# Adafruit_ESP32-S3_8MB_No_PSRAM.net
KiCad netlist of a schematic drawn in EAGLE
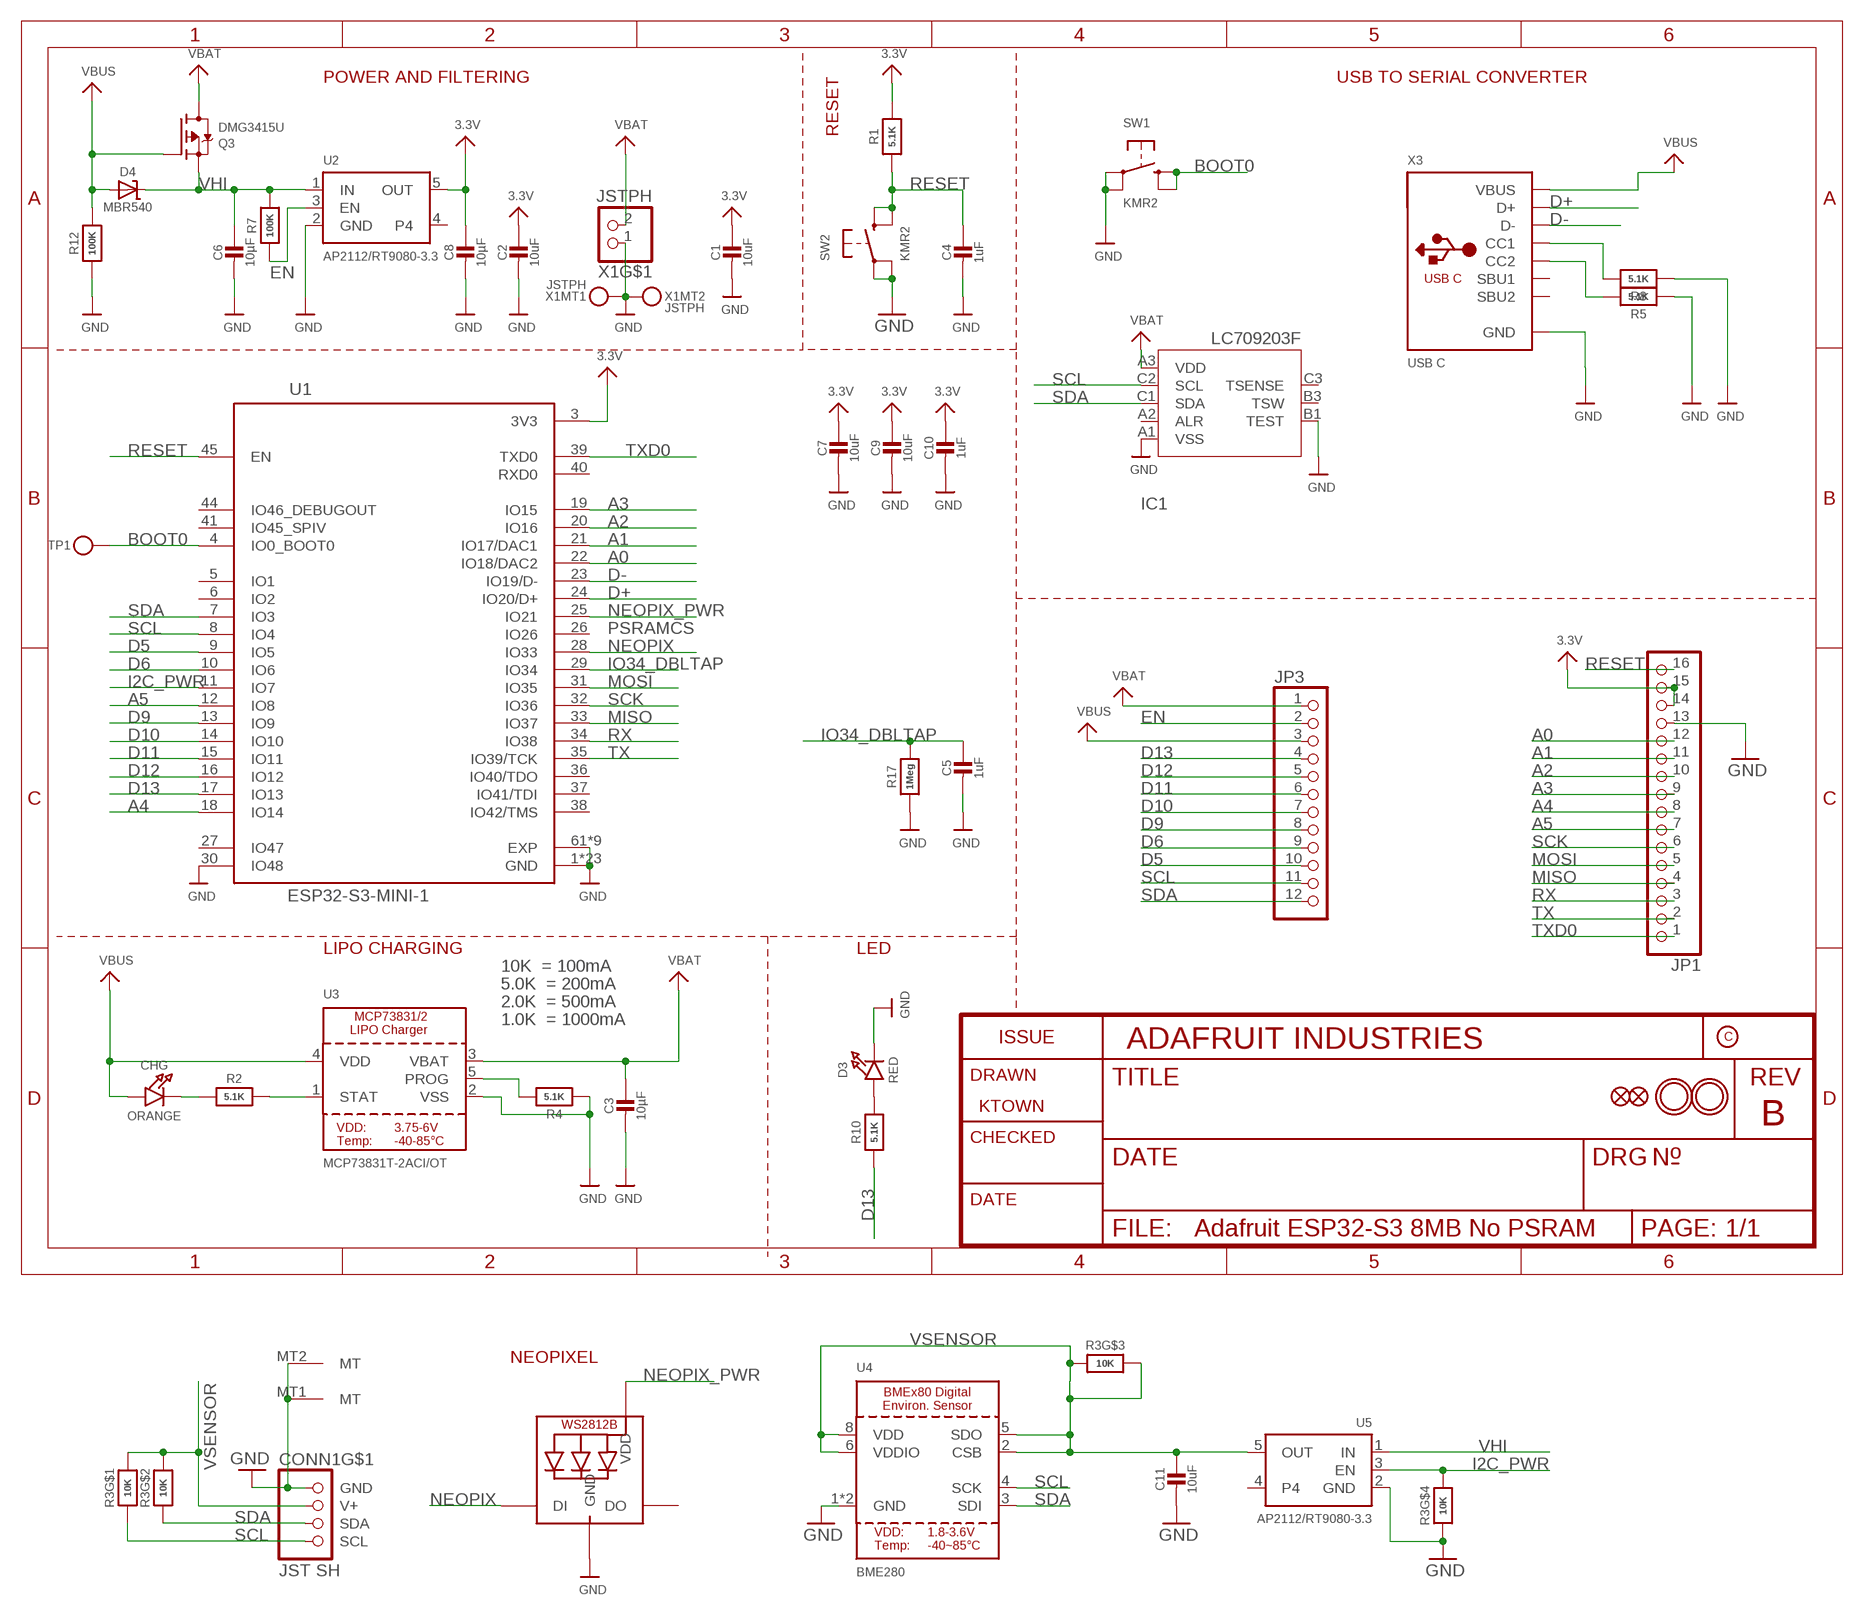
[diagram p0: schematic, sheet 1]

(export (version "E")
  (design (tool "Eeschema 10.0.6"))
  (components
    (comp (ref "C1")
      (value "10uF")
      (footprint "eagle-import:0805-NO")
      (libsource (lib "eagle-import") (part "CAP_CERAMIC0805-NOOUTLINE"))
    )
    (comp (ref "C2")
      (value "10uF")
      (footprint "eagle-import:0805-NO")
      (libsource (lib "eagle-import") (part "CAP_CERAMIC0805-NOOUTLINE"))
    )
    (comp (ref "C3")
      (value "10µF")
      (footprint "eagle-import:0805-NO")
      (libsource (lib "eagle-import") (part "CAP_CERAMIC0805-NOOUTLINE"))
    )
    (comp (ref "C4")
      (value "1uF")
      (footprint "eagle-import:0603-NO")
      (libsource (lib "eagle-import") (part "CAP_CERAMIC0603_NO"))
    )
    (comp (ref "C5")
      (value "1uF")
      (footprint "eagle-import:0603-NO")
      (libsource (lib "eagle-import") (part "CAP_CERAMIC0603_NO"))
    )
    (comp (ref "C6")
      (value "10µF")
      (footprint "eagle-import:0805-NO")
      (libsource (lib "eagle-import") (part "CAP_CERAMIC0805-NOOUTLINE"))
    )
    (comp (ref "C7")
      (value "10uF")
      (footprint "eagle-import:0805-NO")
      (libsource (lib "eagle-import") (part "CAP_CERAMIC0805-NOOUTLINE"))
    )
    (comp (ref "C8")
      (value "10µF")
      (footprint "eagle-import:0805-NO")
      (fields (field (name "REV") "C"))
      (libsource (lib "eagle-import") (part "CAP_CERAMIC0805-NOOUTLINE"))
    )
    (comp (ref "C9")
      (value "10uF")
      (footprint "eagle-import:0805-NO")
      (libsource (lib "eagle-import") (part "CAP_CERAMIC0805-NOOUTLINE"))
    )
    (comp (ref "C10")
      (value "1uF")
      (footprint "eagle-import:0603-NO")
      (libsource (lib "eagle-import") (part "CAP_CERAMIC0603_NO"))
    )
    (comp (ref "C11")
      (value "10uF")
      (footprint "eagle-import:_0805MP")
      (libsource (lib "eagle-import") (part "CAP_CERAMIC_0805MP"))
    )
    (comp (ref "CHG")
      (value "ORANGE")
      (footprint "eagle-import:CHIPLED_0603_NOOUTLINE")
      (libsource (lib "eagle-import") (part "LED0603_NOOUTLINE"))
    )
    (comp (ref "CONN1")
      (value "JST SH")
      (footprint "eagle-import:JST_SH4_RA")
      (libsource (lib "eagle-import") (part "STEMMA_I2C_QTRA"))
    )
    (comp (ref "D3")
      (value "RED")
      (footprint "eagle-import:CHIPLED_0603_NOOUTLINE")
      (libsource (lib "eagle-import") (part "LED0603_NOOUTLINE"))
    )
    (comp (ref "D4")
      (value "MBR540")
      (footprint "eagle-import:SOD-123")
      (libsource (lib "eagle-import") (part "DIODE-SCHOTTKYSOD-123"))
    )
    (comp (ref "IC1")
      (value "LC709203F/MH")
      (footprint "eagle-import:WLCSP9")
      (libsource (lib "eagle-import") (part "LC709203F/MH"))
    )
    (comp (ref "JP1")
      (value "HEADER-1X16ROUND")
      (footprint "eagle-import:1X16_ROUND")
      (libsource (lib "eagle-import") (part "HEADER-1X16ROUND"))
    )
    (comp (ref "JP3")
      (value "HEADER-1X12")
      (footprint "eagle-import:1X12_ROUND")
      (libsource (lib "eagle-import") (part "HEADER-1X12"))
    )
    (comp (ref "LED1")
      (value "WS2812B_SK6805_1515")
      (footprint "eagle-import:SK6805_1515")
      (libsource (lib "eagle-import") (part "WS2812B_SK6805_1515"))
    )
    (comp (ref "Q3")
      (value "DMG3415U")
      (footprint "eagle-import:SOT23-R")
      (libsource (lib "eagle-import") (part "MOSFET-P"))
    )
    (comp (ref "R1")
      (value "5.1K")
      (footprint "eagle-import:0603-NO")
      (libsource (lib "eagle-import") (part "RESISTOR_0603_NOOUT"))
    )
    (comp (ref "R2")
      (value "5.1K")
      (footprint "eagle-import:0603-NO")
      (libsource (lib "eagle-import") (part "RESISTOR_0603_NOOUT"))
    )
    (comp (ref "R3")
      (value "10K")
      (footprint "eagle-import:RESPACK_4X0603")
      (libsource (lib "eagle-import") (part "RESISTOR_4PACK"))
    )
    (comp (ref "R4")
      (value "5.1K")
      (footprint "eagle-import:0603-NO")
      (libsource (lib "eagle-import") (part "RESISTOR_0603_NOOUT"))
    )
    (comp (ref "R5")
      (value "5.1K")
      (footprint "eagle-import:0603-NO")
      (libsource (lib "eagle-import") (part "RESISTOR_0603_NOOUT"))
    )
    (comp (ref "R7")
      (value "100K")
      (footprint "eagle-import:0603-NO")
      (libsource (lib "eagle-import") (part "RESISTOR_0603_NOOUT"))
    )
    (comp (ref "R8")
      (value "5.1K")
      (footprint "eagle-import:0603-NO")
      (libsource (lib "eagle-import") (part "RESISTOR_0603_NOOUT"))
    )
    (comp (ref "R10")
      (value "5.1K")
      (footprint "eagle-import:0603-NO")
      (libsource (lib "eagle-import") (part "RESISTOR_0603_NOOUT"))
    )
    (comp (ref "R12")
      (value "100K")
      (footprint "eagle-import:0603-NO")
      (libsource (lib "eagle-import") (part "RESISTOR_0603_NOOUT"))
    )
    (comp (ref "R17")
      (value "1Meg")
      (footprint "eagle-import:0603-NO")
      (libsource (lib "eagle-import") (part "RESISTOR_0603_NOOUT"))
    )
    (comp (ref "SW1")
      (value "KMR2")
      (footprint "eagle-import:BTN_KMR2_4.6X2.8")
      (libsource (lib "eagle-import") (part "SWITCH_TACT_SMT4.6X2.8"))
    )
    (comp (ref "SW2")
      (value "KMR2")
      (footprint "eagle-import:BTN_KMR2_4.6X2.8")
      (libsource (lib "eagle-import") (part "SWITCH_TACT_SMT4.6X2.8"))
    )
    (comp (ref "TP1")
      (value "TESTPOINTROUND1.5MMNO")
      (footprint "eagle-import:TESTPOINT_ROUND_1.5MM_NO")
      (libsource (lib "eagle-import") (part "TESTPOINTROUND1.5MMNO"))
    )
    (comp (ref "U$31")
      (value "MOUNTINGHOLE2.5")
      (footprint "eagle-import:MOUNTINGHOLE_2.5_PLATED")
      (libsource (lib "eagle-import") (part "MOUNTINGHOLE2.5"))
    )
    (comp (ref "U$32")
      (value "MOUNTINGHOLE2.5")
      (footprint "eagle-import:MOUNTINGHOLE_2.5_PLATED")
      (libsource (lib "eagle-import") (part "MOUNTINGHOLE2.5"))
    )
    (comp (ref "U$34")
      (value "FIDUCIAL_1MM")
      (footprint "eagle-import:FIDUCIAL_1MM")
      (libsource (lib "eagle-import") (part "FIDUCIAL_1MM"))
    )
    (comp (ref "U$35")
      (value "FIDUCIAL_1MM")
      (footprint "eagle-import:FIDUCIAL_1MM")
      (libsource (lib "eagle-import") (part "FIDUCIAL_1MM"))
    )
    (comp (ref "U1")
      (value "ESP32-S3-MINI-1")
      (footprint "eagle-import:QFN60_ESP32-S2-MINI-1_EXP")
      (fields
        (field (name "MANUFACTURER_PART_NUMBER") "ESP32-S2-MINI-1")
        (field (name "COPYRIGHT") "Copyright (C) 2018 Accelerated Designs. All rights reserved")
      )
      (libsource (lib "eagle-import") (part "ESP32-S3-MINI-1"))
    )
    (comp (ref "U2")
      (value "AP2112/RT9080-3.3")
      (footprint "eagle-import:SOT23-5")
      (libsource (lib "eagle-import") (part "VREG_SOT23-5"))
    )
    (comp (ref "U3")
      (value "MCP73831T-2ACI/OT")
      (footprint "eagle-import:SOT23-5")
      (libsource (lib "eagle-import") (part "MCP73831/2"))
    )
    (comp (ref "U4")
      (value "BME280")
      (footprint "eagle-import:BME280")
      (libsource (lib "eagle-import") (part "BME280"))
    )
    (comp (ref "U5")
      (value "AP2112/RT9080-3.3")
      (footprint "eagle-import:SOT23-5")
      (libsource (lib "eagle-import") (part "VREG_SOT23-5"))
    )
    (comp (ref "X1")
      (value "JSTPH")
      (footprint "eagle-import:JSTPH2_BATT")
      (libsource (lib "eagle-import") (part "CON_JST_PH_2PIN_MT_BATT"))
    )
    (comp (ref "X3")
      (value "USB C")
      (footprint "eagle-import:USB_C_CUSB31-CFM2AX-01-X")
      (libsource (lib "eagle-import") (part "USB_C"))
    )
  )
  (nets
    (net (code "1") (name "/A0") (class "Default")
      (node (ref "JP1") (pin "12") (pinfunction "12_12") (pintype "passive"))
      (node (ref "U1") (pin "22") (pinfunction "IO18/DAC2_22") (pintype "bidirectional"))
    )
    (net (code "2") (name "/A1") (class "Default")
      (node (ref "JP1") (pin "11") (pinfunction "11_11") (pintype "passive"))
      (node (ref "U1") (pin "21") (pinfunction "IO17/DAC1_21") (pintype "bidirectional"))
    )
    (net (code "3") (name "/A2") (class "Default")
      (node (ref "JP1") (pin "10") (pinfunction "10_10") (pintype "passive"))
      (node (ref "U1") (pin "20") (pinfunction "IO16_20") (pintype "bidirectional"))
    )
    (net (code "4") (name "/A3") (class "Default")
      (node (ref "JP1") (pin "9") (pinfunction "9_9") (pintype "passive"))
      (node (ref "U1") (pin "19") (pinfunction "IO15_19") (pintype "bidirectional"))
    )
    (net (code "5") (name "/A4") (class "Default")
      (node (ref "JP1") (pin "8") (pinfunction "8_8") (pintype "passive"))
      (node (ref "U1") (pin "18") (pinfunction "IO14_18") (pintype "bidirectional"))
    )
    (net (code "6") (name "/A5") (class "Default")
      (node (ref "JP1") (pin "7") (pinfunction "7_7") (pintype "passive"))
      (node (ref "U1") (pin "12") (pinfunction "IO8_12") (pintype "bidirectional"))
    )
    (net (code "7") (name "/BOOT0") (class "Default")
      (node (ref "SW1") (pin "B") (pinfunction "S_B") (pintype "passive"))
      (node (ref "SW1") (pin "B'") (pinfunction "S1_B'") (pintype "passive"))
      (node (ref "TP1") (pin "P$1") (pinfunction "P$1_P$1") (pintype "bidirectional"))
      (node (ref "U1") (pin "4") (pinfunction "IO0_BOOT0_4") (pintype "bidirectional"))
    )
    (net (code "8") (name "/D+") (class "Default")
      (node (ref "U1") (pin "24") (pinfunction "IO20/D+_24") (pintype "bidirectional"))
      (node (ref "X3") (pin "A6") (pinfunction "D+_A6") (pintype "bidirectional"))
      (node (ref "X3") (pin "B6") (pinfunction "D+_B6") (pintype "bidirectional"))
    )
    (net (code "9") (name "/D-") (class "Default")
      (node (ref "U1") (pin "23") (pinfunction "IO19/D-_23") (pintype "bidirectional"))
      (node (ref "X3") (pin "A7") (pinfunction "D-_A7") (pintype "bidirectional"))
      (node (ref "X3") (pin "B7") (pinfunction "D-_B7") (pintype "bidirectional"))
    )
    (net (code "10") (name "/D5") (class "Default")
      (node (ref "JP3") (pin "10") (pinfunction "10_10") (pintype "passive"))
      (node (ref "U1") (pin "9") (pinfunction "IO5_9") (pintype "bidirectional"))
    )
    (net (code "11") (name "/D6") (class "Default")
      (node (ref "JP3") (pin "9") (pinfunction "9_9") (pintype "passive"))
      (node (ref "U1") (pin "10") (pinfunction "IO6_10") (pintype "bidirectional"))
    )
    (net (code "12") (name "/D9") (class "Default")
      (node (ref "JP3") (pin "8") (pinfunction "8_8") (pintype "passive"))
      (node (ref "U1") (pin "13") (pinfunction "IO9_13") (pintype "bidirectional"))
    )
    (net (code "13") (name "/D10") (class "Default")
      (node (ref "JP3") (pin "7") (pinfunction "7_7") (pintype "passive"))
      (node (ref "U1") (pin "14") (pinfunction "IO10_14") (pintype "bidirectional"))
    )
    (net (code "14") (name "/D11") (class "Default")
      (node (ref "JP3") (pin "6") (pinfunction "6_6") (pintype "passive"))
      (node (ref "U1") (pin "15") (pinfunction "IO11_15") (pintype "bidirectional"))
    )
    (net (code "15") (name "/D12") (class "Default")
      (node (ref "JP3") (pin "5") (pinfunction "5_5") (pintype "passive"))
      (node (ref "U1") (pin "16") (pinfunction "IO12_16") (pintype "bidirectional"))
    )
    (net (code "16") (name "/D13") (class "Default")
      (node (ref "JP3") (pin "4") (pinfunction "4_4") (pintype "passive"))
      (node (ref "R10") (pin "1") (pinfunction "1_1") (pintype "passive"))
      (node (ref "U1") (pin "17") (pinfunction "IO13_17") (pintype "bidirectional"))
    )
    (net (code "17") (name "/EN") (class "Default")
      (node (ref "JP3") (pin "2") (pinfunction "2_2") (pintype "passive"))
      (node (ref "R7") (pin "1") (pinfunction "1_1") (pintype "passive"))
      (node (ref "U2") (pin "3") (pinfunction "EN_3") (pintype "input"))
    )
    (net (code "18") (name "/I2C_PWR") (class "Default")
      (node (ref "R3") (pin "5") (pinfunction "2_5") (pintype "passive"))
      (node (ref "U1") (pin "11") (pinfunction "IO7_11") (pintype "bidirectional"))
      (node (ref "U5") (pin "3") (pinfunction "EN_3") (pintype "input"))
    )
    (net (code "19") (name "/IO34_DBLTAP") (class "Default")
      (node (ref "C5") (pin "1") (pinfunction "1_1") (pintype "passive"))
      (node (ref "R17") (pin "2") (pinfunction "2_2") (pintype "passive"))
      (node (ref "U1") (pin "29") (pinfunction "IO34_29") (pintype "input"))
    )
    (net (code "20") (name "/MISO") (class "Default")
      (node (ref "JP1") (pin "4") (pinfunction "4_4") (pintype "passive"))
      (node (ref "U1") (pin "33") (pinfunction "IO37_33") (pintype "bidirectional"))
    )
    (net (code "21") (name "/MOSI") (class "Default")
      (node (ref "JP1") (pin "5") (pinfunction "5_5") (pintype "passive"))
      (node (ref "U1") (pin "31") (pinfunction "IO35_31") (pintype "input"))
    )
    (net (code "22") (name "/NEOPIX") (class "Default")
      (node (ref "LED1") (pin "1") (pinfunction "DI_1") (pintype "input"))
      (node (ref "U1") (pin "28") (pinfunction "IO33_28") (pintype "bidirectional"))
    )
    (net (code "23") (name "/NEOPIX_PWR") (class "Default")
      (node (ref "LED1") (pin "2") (pinfunction "VDD_2") (pintype "power_in"))
      (node (ref "U1") (pin "25") (pinfunction "IO21_25") (pintype "bidirectional"))
    )
    (net (code "24") (name "/RESET") (class "Default")
      (node (ref "C4") (pin "1") (pinfunction "1_1") (pintype "passive"))
      (node (ref "JP1") (pin "16") (pinfunction "16_16") (pintype "passive"))
      (node (ref "R1") (pin "1") (pinfunction "1_1") (pintype "passive"))
      (node (ref "SW2") (pin "B") (pinfunction "S_B") (pintype "passive"))
      (node (ref "SW2") (pin "B'") (pinfunction "S1_B'") (pintype "passive"))
      (node (ref "U1") (pin "45") (pinfunction "EN_45") (pintype "input"))
    )
    (net (code "25") (name "/RX") (class "Default")
      (node (ref "JP1") (pin "3") (pinfunction "3_3") (pintype "passive"))
      (node (ref "U1") (pin "34") (pinfunction "IO38_34") (pintype "bidirectional"))
    )
    (net (code "26") (name "/SCK") (class "Default")
      (node (ref "JP1") (pin "6") (pinfunction "6_6") (pintype "passive"))
      (node (ref "U1") (pin "32") (pinfunction "IO36_32") (pintype "bidirectional"))
    )
    (net (code "27") (name "/SCL") (class "Default")
      (node (ref "CONN1") (pin "4") (pinfunction "SCL_4") (pintype "passive"))
      (node (ref "IC1") (pin "C2") (pinfunction "SCL_C2") (pintype "bidirectional"))
      (node (ref "JP3") (pin "11") (pinfunction "11_11") (pintype "passive"))
      (node (ref "R3") (pin "1") (pinfunction "1_1") (pintype "passive"))
      (node (ref "U1") (pin "8") (pinfunction "IO4_8") (pintype "bidirectional"))
      (node (ref "U4") (pin "4") (pinfunction "SCK_4") (pintype "input"))
    )
    (net (code "28") (name "/SDA") (class "Default")
      (node (ref "CONN1") (pin "3") (pinfunction "SDA_3") (pintype "passive"))
      (node (ref "IC1") (pin "C1") (pinfunction "SDA_C1") (pintype "bidirectional"))
      (node (ref "JP3") (pin "12") (pinfunction "12_12") (pintype "passive"))
      (node (ref "R3") (pin "2") (pinfunction "1_2") (pintype "passive"))
      (node (ref "U1") (pin "7") (pinfunction "IO3_7") (pintype "bidirectional"))
      (node (ref "U4") (pin "3") (pinfunction "SDI_3") (pintype "input"))
    )
    (net (code "29") (name "/TX") (class "Default")
      (node (ref "JP1") (pin "2") (pinfunction "2_2") (pintype "passive"))
      (node (ref "U1") (pin "35") (pinfunction "IO39/TCK_35") (pintype "bidirectional"))
    )
    (net (code "30") (name "/TXD0") (class "Default")
      (node (ref "JP1") (pin "1") (pinfunction "1_1") (pintype "passive"))
      (node (ref "U1") (pin "39") (pinfunction "TXD0_39") (pintype "bidirectional"))
    )
    (net (code "31") (name "/VHI") (class "Default")
      (node (ref "C6") (pin "1") (pinfunction "1_1") (pintype "passive"))
      (node (ref "D4") (pin "C") (pinfunction "C_C") (pintype "passive"))
      (node (ref "Q3") (pin "2") (pinfunction "S_2") (pintype "passive"))
      (node (ref "R7") (pin "2") (pinfunction "2_2") (pintype "passive"))
      (node (ref "U2") (pin "1") (pinfunction "IN_1") (pintype "power_in"))
      (node (ref "U5") (pin "1") (pinfunction "IN_1") (pintype "power_in"))
    )
    (net (code "32") (name "/VSENSOR") (class "Default")
      (node (ref "C11") (pin "1") (pinfunction "1_1") (pintype "passive"))
      (node (ref "CONN1") (pin "2") (pinfunction "V+_2") (pintype "passive"))
      (node (ref "R3") (pin "3") (pinfunction "1_3") (pintype "passive"))
      (node (ref "R3") (pin "6") (pinfunction "2_6") (pintype "passive"))
      (node (ref "R3") (pin "7") (pinfunction "2_7") (pintype "passive"))
      (node (ref "R3") (pin "8") (pinfunction "2_8") (pintype "passive"))
      (node (ref "U4") (pin "2") (pinfunction "CSB_2") (pintype "input"))
      (node (ref "U4") (pin "5") (pinfunction "SDO_5") (pintype "output"))
      (node (ref "U4") (pin "6") (pinfunction "VDDIO_6") (pintype "power_in"))
      (node (ref "U4") (pin "8") (pinfunction "VDD_8") (pintype "power_in"))
      (node (ref "U5") (pin "5") (pinfunction "OUT_5") (pintype "power_in"))
    )
    (net (code "33") (name "3.3V") (class "Default")
      (node (ref "C1") (pin "1") (pinfunction "1_1") (pintype "passive"))
      (node (ref "C10") (pin "1") (pinfunction "1_1") (pintype "passive"))
      (node (ref "C2") (pin "1") (pinfunction "1_1") (pintype "passive"))
      (node (ref "C7") (pin "1") (pinfunction "1_1") (pintype "passive"))
      (node (ref "C8") (pin "1") (pinfunction "1_1") (pintype "passive"))
      (node (ref "C9") (pin "1") (pinfunction "1_1") (pintype "passive"))
      (node (ref "JP1") (pin "14") (pinfunction "14_14") (pintype "passive"))
      (node (ref "JP1") (pin "15") (pinfunction "15_15") (pintype "passive"))
      (node (ref "R1") (pin "2") (pinfunction "2_2") (pintype "passive"))
      (node (ref "U1") (pin "3") (pinfunction "3V3_3") (pintype "power_in"))
      (node (ref "U2") (pin "5") (pinfunction "OUT_5") (pintype "power_in"))
    )
    (net (code "34") (name "GND") (class "Default")
      (node (ref "C1") (pin "2") (pinfunction "2_2") (pintype "passive"))
      (node (ref "C10") (pin "2") (pinfunction "2_2") (pintype "passive"))
      (node (ref "C11") (pin "2") (pinfunction "2_2") (pintype "passive"))
      (node (ref "C2") (pin "2") (pinfunction "2_2") (pintype "passive"))
      (node (ref "C3") (pin "2") (pinfunction "2_2") (pintype "passive"))
      (node (ref "C4") (pin "2") (pinfunction "2_2") (pintype "passive"))
      (node (ref "C5") (pin "2") (pinfunction "2_2") (pintype "passive"))
      (node (ref "C6") (pin "2") (pinfunction "2_2") (pintype "passive"))
      (node (ref "C7") (pin "2") (pinfunction "2_2") (pintype "passive"))
      (node (ref "C8") (pin "2") (pinfunction "2_2") (pintype "passive"))
      (node (ref "C9") (pin "2") (pinfunction "2_2") (pintype "passive"))
      (node (ref "CONN1") (pin "1") (pinfunction "GND_1") (pintype "passive"))
      (node (ref "CONN1") (pin "MT1") (pinfunction "MT_MT1") (pintype "bidirectional"))
      (node (ref "CONN1") (pin "MT2") (pinfunction "MT_MT2") (pintype "bidirectional"))
      (node (ref "D3") (pin "C") (pinfunction "C_C") (pintype "passive"))
      (node (ref "IC1") (pin "A1") (pinfunction "VSS_A1") (pintype "power_in"))
      (node (ref "IC1") (pin "B1") (pinfunction "TEST_B1") (pintype "input"))
      (node (ref "JP1") (pin "13") (pinfunction "13_13") (pintype "passive"))
      (node (ref "LED1") (pin "4") (pinfunction "GND_4") (pintype "power_in"))
      (node (ref "R12") (pin "1") (pinfunction "1_1") (pintype "passive"))
      (node (ref "R17") (pin "1") (pinfunction "1_1") (pintype "passive"))
      (node (ref "R3") (pin "4") (pinfunction "1_4") (pintype "passive"))
      (node (ref "R4") (pin "1") (pinfunction "1_1") (pintype "passive"))
      (node (ref "R5") (pin "1") (pinfunction "1_1") (pintype "passive"))
      (node (ref "R8") (pin "1") (pinfunction "1_1") (pintype "passive"))
      (node (ref "SW1") (pin "A") (pinfunction "P_A") (pintype "passive"))
      (node (ref "SW1") (pin "A'") (pinfunction "P1_A'") (pintype "passive"))
      (node (ref "SW2") (pin "A") (pinfunction "P_A") (pintype "passive"))
      (node (ref "SW2") (pin "A'") (pinfunction "P1_A'") (pintype "passive"))
      (node (ref "U1") (pin "1") (pinfunction "GND_1") (pintype "power_in"))
      (node (ref "U1") (pin "2") (pinfunction "GND_2") (pintype "power_in"))
      (node (ref "U1") (pin "30") (pinfunction "IO48_30") (pintype "bidirectional"))
      (node (ref "U1") (pin "42") (pinfunction "GND_42") (pintype "power_in"))
      (node (ref "U1") (pin "43") (pinfunction "GND_43") (pintype "power_in"))
      (node (ref "U1") (pin "46") (pinfunction "GND_46") (pintype "power_in"))
      (node (ref "U1") (pin "47") (pinfunction "GND_47") (pintype "power_in"))
      (node (ref "U1") (pin "48") (pinfunction "GND_48") (pintype "power_in"))
      (node (ref "U1") (pin "49") (pinfunction "GND_49") (pintype "power_in"))
      (node (ref "U1") (pin "50") (pinfunction "GND_50") (pintype "power_in"))
      (node (ref "U1") (pin "51") (pinfunction "GND_51") (pintype "power_in"))
      (node (ref "U1") (pin "52") (pinfunction "GND_52") (pintype "power_in"))
      (node (ref "U1") (pin "53") (pinfunction "GND_53") (pintype "power_in"))
      (node (ref "U1") (pin "54") (pinfunction "GND_54") (pintype "power_in"))
      (node (ref "U1") (pin "55") (pinfunction "GND_55") (pintype "power_in"))
      (node (ref "U1") (pin "56") (pinfunction "GND_56") (pintype "power_in"))
      (node (ref "U1") (pin "57") (pinfunction "GND_57") (pintype "power_in"))
      (node (ref "U1") (pin "58") (pinfunction "GND_58") (pintype "power_in"))
      (node (ref "U1") (pin "59") (pinfunction "GND_59") (pintype "power_in"))
      (node (ref "U1") (pin "60") (pinfunction "GND_60") (pintype "power_in"))
      (node (ref "U1") (pin "61") (pinfunction "EXP_61") (pintype "power_in"))
      (node (ref "U1") (pin "62") (pinfunction "GND_62") (pintype "power_in"))
      (node (ref "U1") (pin "63") (pinfunction "GND_63") (pintype "power_in"))
      (node (ref "U1") (pin "64") (pinfunction "GND_64") (pintype "power_in"))
      (node (ref "U1") (pin "65") (pinfunction "GND_65") (pintype "power_in"))
      (node (ref "U1") (pin "66") (pinfunction "EXP_66") (pintype "power_in"))
      (node (ref "U1") (pin "67") (pinfunction "EXP_67") (pintype "power_in"))
      (node (ref "U1") (pin "68") (pinfunction "EXP_68") (pintype "power_in"))
      (node (ref "U1") (pin "69") (pinfunction "EXP_69") (pintype "power_in"))
      (node (ref "U1") (pin "70") (pinfunction "EXP_70") (pintype "power_in"))
      (node (ref "U1") (pin "71") (pinfunction "EXP_71") (pintype "power_in"))
      (node (ref "U1") (pin "72") (pinfunction "EXP_72") (pintype "power_in"))
      (node (ref "U1") (pin "73") (pinfunction "EXP_73") (pintype "power_in"))
      (node (ref "U2") (pin "2") (pinfunction "GND_2") (pintype "power_in"))
      (node (ref "U3") (pin "2") (pinfunction "VSS_2") (pintype "power_in"))
      (node (ref "U4") (pin "1") (pinfunction "GND_1") (pintype "power_in"))
      (node (ref "U4") (pin "7") (pinfunction "GND_7") (pintype "power_in"))
      (node (ref "U5") (pin "2") (pinfunction "GND_2") (pintype "power_in"))
      (node (ref "X1") (pin "1") (pinfunction "1_1") (pintype "passive"))
      (node (ref "X1") (pin "NC1") (pinfunction "P$1_NC1") (pintype "bidirectional"))
      (node (ref "X1") (pin "NC2") (pinfunction "P$1_NC2") (pintype "bidirectional"))
      (node (ref "X3") (pin "A1B12") (pinfunction "GND_A1B12") (pintype "power_in"))
      (node (ref "X3") (pin "B1A12") (pinfunction "GND_B1A12") (pintype "power_in"))
    )
    (net (code "35") (name "Net-(CHG-PadC)") (class "Default")
      (node (ref "CHG") (pin "C") (pinfunction "C_C") (pintype "passive"))
      (node (ref "R2") (pin "1") (pinfunction "1_1") (pintype "passive"))
    )
    (net (code "36") (name "Net-(D3-PadA)") (class "Default")
      (node (ref "D3") (pin "A") (pinfunction "A_A") (pintype "passive"))
      (node (ref "R10") (pin "2") (pinfunction "2_2") (pintype "passive"))
    )
    (net (code "37") (name "Net-(U3-PROG)") (class "Default")
      (node (ref "R4") (pin "2") (pinfunction "2_2") (pintype "passive"))
      (node (ref "U3") (pin "5") (pinfunction "PROG_5") (pintype "input"))
    )
    (net (code "38") (name "Net-(U3-STAT)") (class "Default")
      (node (ref "R2") (pin "2") (pinfunction "2_2") (pintype "passive"))
      (node (ref "U3") (pin "1") (pinfunction "STAT_1") (pintype "output"))
    )
    (net (code "39") (name "Net-(X3-CC1)") (class "Default")
      (node (ref "R8") (pin "2") (pinfunction "2_2") (pintype "passive"))
      (node (ref "X3") (pin "A5") (pinfunction "CC1_A5") (pintype "bidirectional"))
    )
    (net (code "40") (name "Net-(X3-CC2)") (class "Default")
      (node (ref "R5") (pin "2") (pinfunction "2_2") (pintype "passive"))
      (node (ref "X3") (pin "B5") (pinfunction "CC2_B5") (pintype "bidirectional"))
    )
    (net (code "41") (name "VBAT") (class "Default")
      (node (ref "C3") (pin "1") (pinfunction "1_1") (pintype "passive"))
      (node (ref "IC1") (pin "A3") (pinfunction "VDD_A3") (pintype "power_in"))
      (node (ref "JP3") (pin "1") (pinfunction "1_1") (pintype "passive"))
      (node (ref "Q3") (pin "3") (pinfunction "D_3") (pintype "passive"))
      (node (ref "U3") (pin "3") (pinfunction "VBAT_3") (pintype "power_in"))
      (node (ref "X1") (pin "2") (pinfunction "2_2") (pintype "passive"))
    )
    (net (code "42") (name "VBUS") (class "Default")
      (node (ref "CHG") (pin "A") (pinfunction "A_A") (pintype "passive"))
      (node (ref "D4") (pin "A") (pinfunction "A_A") (pintype "passive"))
      (node (ref "JP3") (pin "3") (pinfunction "3_3") (pintype "passive"))
      (node (ref "Q3") (pin "1") (pinfunction "G_1") (pintype "passive"))
      (node (ref "R12") (pin "2") (pinfunction "2_2") (pintype "passive"))
      (node (ref "U3") (pin "4") (pinfunction "VDD_4") (pintype "power_in"))
      (node (ref "X3") (pin "A4B9") (pinfunction "VBUS_A4B9") (pintype "power_in"))
      (node (ref "X3") (pin "B4A9") (pinfunction "VBUS_B4A9") (pintype "power_in"))
    )
    (net (code "43") (name "unconnected-(IC1-ALR-PadA2)") (class "Default")
      (node (ref "IC1") (pin "A2") (pinfunction "ALR_A2") (pintype "output"))
    )
    (net (code "44") (name "unconnected-(IC1-TSENSE-PadC3)") (class "Default")
      (node (ref "IC1") (pin "C3") (pinfunction "TSENSE_C3") (pintype "passive"))
    )
    (net (code "45") (name "unconnected-(IC1-TSW-PadB3)") (class "Default")
      (node (ref "IC1") (pin "B3") (pinfunction "TSW_B3") (pintype "output"))
    )
    (net (code "46") (name "unconnected-(LED1-DO-Pad3)") (class "Default")
      (node (ref "LED1") (pin "3") (pinfunction "DO_3") (pintype "output"))
    )
    (net (code "47") (name "unconnected-(U1-IO1-Pad5)") (class "Default")
      (node (ref "U1") (pin "5") (pinfunction "IO1_5") (pintype "bidirectional"))
    )
    (net (code "48") (name "unconnected-(U1-IO2-Pad6)") (class "Default")
      (node (ref "U1") (pin "6") (pinfunction "IO2_6") (pintype "bidirectional"))
    )
    (net (code "49") (name "unconnected-(U1-IO26-Pad26)") (class "Default")
      (node (ref "U1") (pin "26") (pinfunction "IO26_26") (pintype "bidirectional"))
    )
    (net (code "50") (name "unconnected-(U1-IO40{slash}TDO-Pad36)") (class "Default")
      (node (ref "U1") (pin "36") (pinfunction "IO40/TDO_36") (pintype "bidirectional"))
    )
    (net (code "51") (name "unconnected-(U1-IO41{slash}TDI-Pad37)") (class "Default")
      (node (ref "U1") (pin "37") (pinfunction "IO41/TDI_37") (pintype "bidirectional"))
    )
    (net (code "52") (name "unconnected-(U1-IO42{slash}TMS-Pad38)") (class "Default")
      (node (ref "U1") (pin "38") (pinfunction "IO42/TMS_38") (pintype "bidirectional"))
    )
    (net (code "53") (name "unconnected-(U1-IO45_SPIV-Pad41)") (class "Default")
      (node (ref "U1") (pin "41") (pinfunction "IO45_SPIV_41") (pintype "bidirectional"))
    )
    (net (code "54") (name "unconnected-(U1-IO46_DEBUGOUT-Pad44)") (class "Default")
      (node (ref "U1") (pin "44") (pinfunction "IO46_DEBUGOUT_44") (pintype "input"))
    )
    (net (code "55") (name "unconnected-(U1-IO47-Pad27)") (class "Default")
      (node (ref "U1") (pin "27") (pinfunction "IO47_27") (pintype "bidirectional"))
    )
    (net (code "56") (name "unconnected-(U1-RXD0-Pad40)") (class "Default")
      (node (ref "U1") (pin "40") (pinfunction "RXD0_40") (pintype "bidirectional"))
    )
    (net (code "57") (name "unconnected-(U2-P4-Pad4)") (class "Default")
      (node (ref "U2") (pin "4") (pinfunction "P4_4") (pintype "bidirectional"))
    )
    (net (code "58") (name "unconnected-(U5-P4-Pad4)") (class "Default")
      (node (ref "U5") (pin "4") (pinfunction "P4_4") (pintype "bidirectional"))
    )
    (net (code "59") (name "unconnected-(X3-SBU1-PadA8)") (class "Default")
      (node (ref "X3") (pin "A8") (pinfunction "SBU1_A8") (pintype "bidirectional"))
    )
    (net (code "60") (name "unconnected-(X3-SBU2-PadB8)") (class "Default")
      (node (ref "X3") (pin "B8") (pinfunction "SBU2_B8") (pintype "bidirectional"))
    )
  )
)
